# FMC_HPC2.net
KiCad netlist of a schematic drawn in Altium Designer
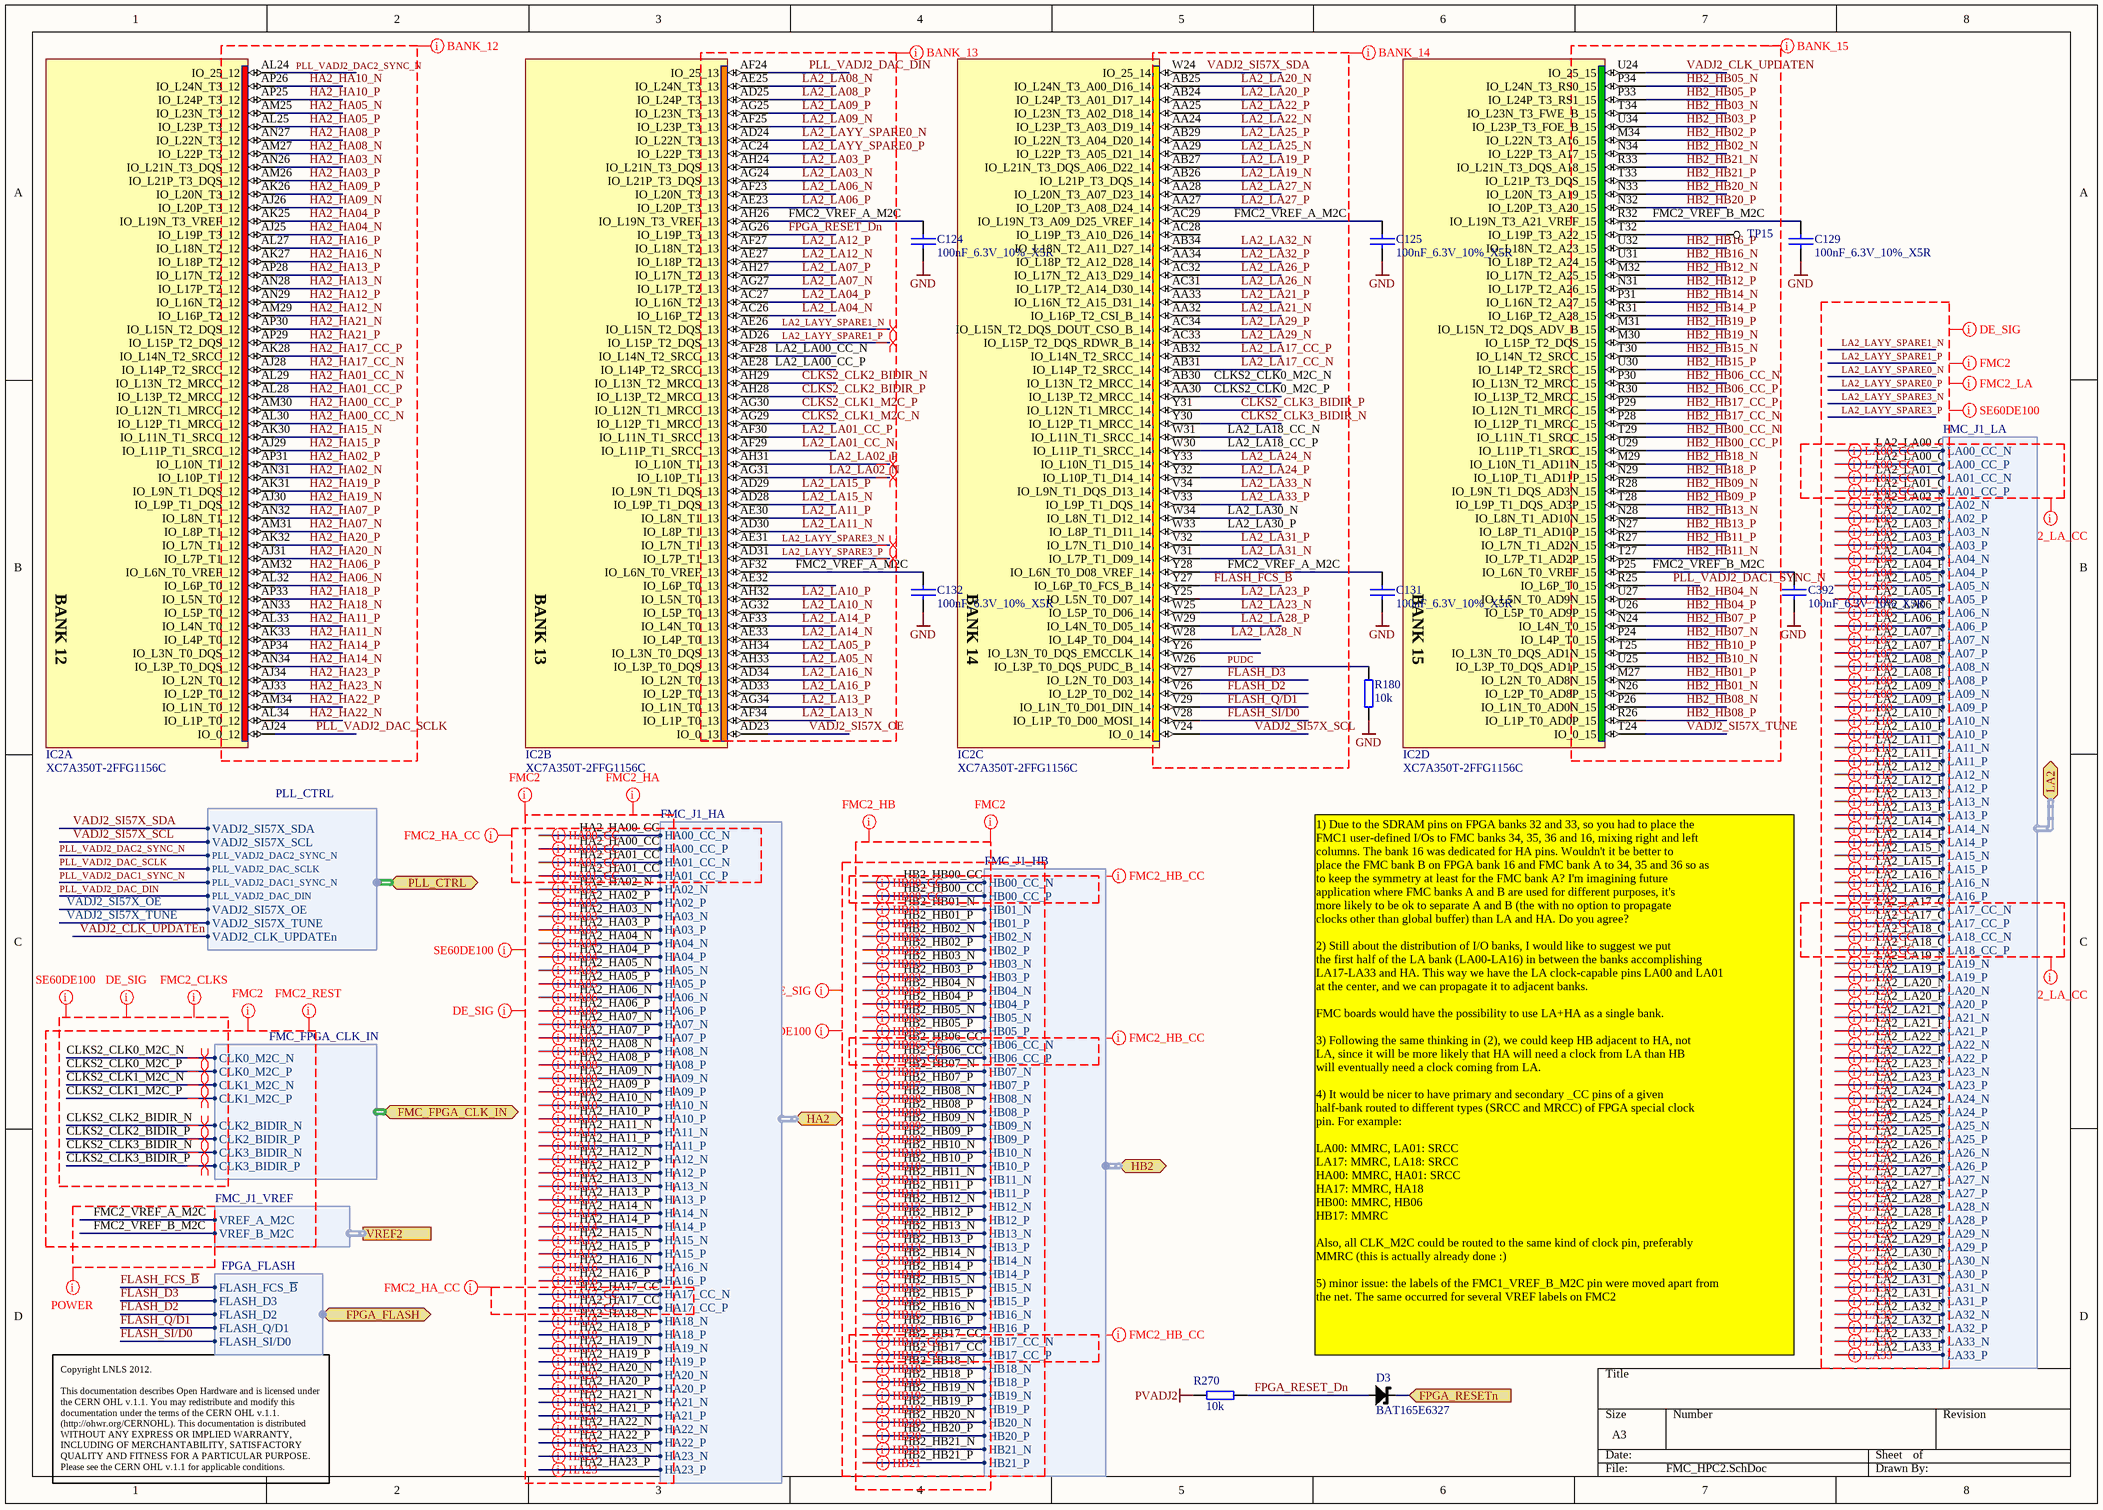
[diagram p0: FMC_HPC2.SchDoc]

(export (version "E")
  (design (tool "Eeschema 10.0.6"))
  (components
    (comp (ref "C124")
      (value "100nF_6.3V_10%_X5R")
      (footprint "0201C")
      (description "Capacitor SMD")
      (libsource (lib "LIBRARY_SCH") (part "CAP_SMD_0201"))
    )
    (comp (ref "C125")
      (value "100nF_6.3V_10%_X5R")
      (footprint "0201C")
      (description "Capacitor SMD")
      (libsource (lib "LIBRARY_SCH") (part "CAP_SMD_0201"))
    )
    (comp (ref "C129")
      (value "100nF_6.3V_10%_X5R")
      (footprint "0201C")
      (description "Capacitor SMD")
      (libsource (lib "LIBRARY_SCH") (part "CAP_SMD_0201"))
    )
    (comp (ref "C131")
      (value "100nF_6.3V_10%_X5R")
      (footprint "0201C")
      (description "Capacitor SMD")
      (libsource (lib "LIBRARY_SCH") (part "CAP_SMD_0201"))
    )
    (comp (ref "C132")
      (value "100nF_6.3V_10%_X5R")
      (footprint "0201C")
      (description "Capacitor SMD")
      (libsource (lib "LIBRARY_SCH") (part "CAP_SMD_0201"))
    )
    (comp (ref "C392")
      (value "100nF_6.3V_10%_X5R")
      (footprint "0201C")
      (description "Capacitor SMD")
      (libsource (lib "LIBRARY_SCH") (part "CAP_SMD_0201"))
    )
    (comp (ref "D3")
      (value "BAT165E6327")
      (footprint "SOD323")
      (description "500mA, 40V, Shottky Diode")
      (libsource (lib "LIBRARY_SCH") (part "D_BAT165"))
    )
    (comp (ref "IC2")
      (value "XC7A350T-2FFG1156C")
      (footprint "BGA1156C100P34X34_3500X3500X335")
      (description "Artix-6 FPGA, 16 GTPs, 600 User I/Os, 1156-Pin BGA, Speed Grade 2, Commercial Grade, Pb-Free")
      (fields (field (name "MANUFACTURER") "XILINX") (field (name "AUTHOR") "CERN DEM JLC"))
      (libsource (lib "AMC_FMC_Carrier") (part "XC7A350T-2FFG1156C"))
    )
    (comp (ref "R180")
      (value "10k")
      (footprint "0402R")
      (description "SMD Resistor")
      (libsource (lib "LIBRARY_SCH") (part "RES_0402"))
    )
    (comp (ref "R270")
      (value "10k")
      (footprint "0402R")
      (description "SMD Resistor")
      (libsource (lib "LIBRARY_SCH") (part "RES_0402"))
    )
    (comp (ref "TP15")
      (value "TP")
      (footprint "TP_large")
      (description "Testpoint")
      (libsource (lib "LIBRARY_SCH") (part "TP"))
    )
  )
  (nets
    (net (code "8") (name "/CLKS2_CLK0_M2C_N") (class "Default")
      (node (ref "IC2") (pin "AB30") (pinfunction "IO_L13N_T2_MRCC_14_AB30") (pintype "bidirectional"))
    )
    (net (code "9") (name "/CLKS2_CLK0_M2C_P") (class "Default")
      (node (ref "IC2") (pin "AA30") (pinfunction "IO_L13P_T2_MRCC_14_AA30") (pintype "bidirectional"))
    )
    (net (code "10") (name "/CLKS2_CLK1_M2C_N") (class "Default")
      (node (ref "IC2") (pin "AG29") (pinfunction "IO_L12P_T1_MRCC_13_AG29") (pintype "bidirectional"))
    )
    (net (code "11") (name "/CLKS2_CLK1_M2C_P") (class "Default")
      (node (ref "IC2") (pin "AG30") (pinfunction "IO_L12N_T1_MRCC_13_AG30") (pintype "bidirectional"))
    )
    (net (code "12") (name "/CLKS2_CLK2_BIDIR_N") (class "Default")
      (node (ref "IC2") (pin "AH29") (pinfunction "IO_L13N_T2_MRCC_13_AH29") (pintype "bidirectional"))
    )
    (net (code "13") (name "/CLKS2_CLK2_BIDIR_P") (class "Default")
      (node (ref "IC2") (pin "AH28") (pinfunction "IO_L13P_T2_MRCC_13_AH28") (pintype "bidirectional"))
    )
    (net (code "14") (name "/CLKS2_CLK3_BIDIR_N") (class "Default")
      (node (ref "IC2") (pin "Y30") (pinfunction "IO_L12P_T1_MRCC_14_Y30") (pintype "bidirectional"))
    )
    (net (code "15") (name "/CLKS2_CLK3_BIDIR_P") (class "Default")
      (node (ref "IC2") (pin "Y31") (pinfunction "IO_L12N_T1_MRCC_14_Y31") (pintype "bidirectional"))
    )
    (net (code "16") (name "/FLASH_D2") (class "Default")
      (node (ref "IC2") (pin "V26") (pinfunction "IO_L2P_T0_D02_14_V26") (pintype "bidirectional"))
    )
    (net (code "17") (name "/FLASH_D3") (class "Default")
      (node (ref "IC2") (pin "V27") (pinfunction "IO_L2N_T0_D03_14_V27") (pintype "bidirectional"))
    )
    (net (code "18") (name "/FLASH_FCS_~{B}") (class "Default")
      (node (ref "IC2") (pin "Y27") (pinfunction "IO_L6P_T0_FCS_B_14_Y27") (pintype "bidirectional"))
    )
    (net (code "19") (name "/FLASH_Q{slash}D1") (class "Default")
      (node (ref "IC2") (pin "V29") (pinfunction "IO_L1N_T0_D01_DIN_14_V29") (pintype "bidirectional"))
    )
    (net (code "20") (name "/FLASH_SI{slash}D0") (class "Default")
      (node (ref "IC2") (pin "V28") (pinfunction "IO_L1P_T0_D00_MOSI_14_V28") (pintype "bidirectional"))
    )
    (net (code "21") (name "/FMC2_VREF_A_M2C") (class "Default")
      (node (ref "C124") (pin "1") (pinfunction "1_1") (pintype "passive"))
      (node (ref "C125") (pin "1") (pinfunction "1_1") (pintype "passive"))
      (node (ref "C131") (pin "1") (pinfunction "1_1") (pintype "passive"))
      (node (ref "C132") (pin "1") (pinfunction "1_1") (pintype "passive"))
      (node (ref "IC2") (pin "AC29") (pinfunction "IO_L19N_T3_A09_D25_VREF_14_AC29") (pintype "bidirectional"))
      (node (ref "IC2") (pin "AF32") (pinfunction "IO_L6N_T0_VREF_13_AF32") (pintype "bidirectional"))
      (node (ref "IC2") (pin "AH26") (pinfunction "IO_L19N_T3_VREF_13_AH26") (pintype "bidirectional"))
      (node (ref "IC2") (pin "Y28") (pinfunction "IO_L6N_T0_D08_VREF_14_Y28") (pintype "bidirectional"))
    )
    (net (code "22") (name "/FMC2_VREF_B_M2C") (class "Default")
      (node (ref "C129") (pin "1") (pinfunction "1_1") (pintype "passive"))
      (node (ref "C392") (pin "1") (pinfunction "1_1") (pintype "passive"))
      (node (ref "IC2") (pin "P25") (pinfunction "IO_L6N_T0_VREF_15_P25") (pintype "bidirectional"))
      (node (ref "IC2") (pin "R32") (pinfunction "IO_L19N_T3_A21_VREF_15_R32") (pintype "bidirectional"))
    )
    (net (code "23") (name "/FPGA_RESET_Dn") (class "Default")
      (node (ref "D3") (pin "A") (pinfunction "A_A") (pintype "passive"))
      (node (ref "IC2") (pin "AG26") (pinfunction "IO_L19P_T3_13_AG26") (pintype "bidirectional"))
      (node (ref "R270") (pin "2") (pinfunction "2_2") (pintype "passive"))
    )
    (net (code "24") (name "/FPGA_RESETn") (class "Default")
      (node (ref "D3") (pin "K") (pinfunction "K_K") (pintype "passive"))
    )
    (net (code "25") (name "/HA2_HA00_CC_N") (class "Default")
      (node (ref "IC2") (pin "AL30") (pinfunction "IO_L12P_T1_MRCC_12_AL30") (pintype "bidirectional"))
    )
    (net (code "26") (name "/HA2_HA00_CC_P") (class "Default")
      (node (ref "IC2") (pin "AM30") (pinfunction "IO_L12N_T1_MRCC_12_AM30") (pintype "bidirectional"))
    )
    (net (code "27") (name "/HA2_HA01_CC_N") (class "Default")
      (node (ref "IC2") (pin "AL29") (pinfunction "IO_L13N_T2_MRCC_12_AL29") (pintype "bidirectional"))
    )
    (net (code "28") (name "/HA2_HA01_CC_P") (class "Default")
      (node (ref "IC2") (pin "AL28") (pinfunction "IO_L13P_T2_MRCC_12_AL28") (pintype "bidirectional"))
    )
    (net (code "29") (name "/HA2_HA02_N") (class "Default")
      (node (ref "IC2") (pin "AN31") (pinfunction "IO_L10P_T1_12_AN31") (pintype "bidirectional"))
    )
    (net (code "30") (name "/HA2_HA02_P") (class "Default")
      (node (ref "IC2") (pin "AP31") (pinfunction "IO_L10N_T1_12_AP31") (pintype "bidirectional"))
    )
    (net (code "31") (name "/HA2_HA03_N") (class "Default")
      (node (ref "IC2") (pin "AN26") (pinfunction "IO_L21N_T3_DQS_12_AN26") (pintype "bidirectional"))
    )
    (net (code "32") (name "/HA2_HA03_P") (class "Default")
      (node (ref "IC2") (pin "AM26") (pinfunction "IO_L21P_T3_DQS_12_AM26") (pintype "bidirectional"))
    )
    (net (code "33") (name "/HA2_HA04_N") (class "Default")
      (node (ref "IC2") (pin "AJ25") (pinfunction "IO_L19P_T3_12_AJ25") (pintype "bidirectional"))
    )
    (net (code "34") (name "/HA2_HA04_P") (class "Default")
      (node (ref "IC2") (pin "AK25") (pinfunction "IO_L19N_T3_VREF_12_AK25") (pintype "bidirectional"))
    )
    (net (code "35") (name "/HA2_HA05_N") (class "Default")
      (node (ref "IC2") (pin "AM25") (pinfunction "IO_L23N_T3_12_AM25") (pintype "bidirectional"))
    )
    (net (code "36") (name "/HA2_HA05_P") (class "Default")
      (node (ref "IC2") (pin "AL25") (pinfunction "IO_L23P_T3_12_AL25") (pintype "bidirectional"))
    )
    (net (code "37") (name "/HA2_HA06_N") (class "Default")
      (node (ref "IC2") (pin "AL32") (pinfunction "IO_L6P_T0_12_AL32") (pintype "bidirectional"))
    )
    (net (code "38") (name "/HA2_HA06_P") (class "Default")
      (node (ref "IC2") (pin "AM32") (pinfunction "IO_L6N_T0_VREF_12_AM32") (pintype "bidirectional"))
    )
    (net (code "39") (name "/HA2_HA07_N") (class "Default")
      (node (ref "IC2") (pin "AM31") (pinfunction "IO_L8P_T1_12_AM31") (pintype "bidirectional"))
    )
    (net (code "40") (name "/HA2_HA07_P") (class "Default")
      (node (ref "IC2") (pin "AN32") (pinfunction "IO_L8N_T1_12_AN32") (pintype "bidirectional"))
    )
    (net (code "41") (name "/HA2_HA08_N") (class "Default")
      (node (ref "IC2") (pin "AM27") (pinfunction "IO_L22P_T3_12_AM27") (pintype "bidirectional"))
    )
    (net (code "42") (name "/HA2_HA08_P") (class "Default")
      (node (ref "IC2") (pin "AN27") (pinfunction "IO_L22N_T3_12_AN27") (pintype "bidirectional"))
    )
    (net (code "43") (name "/HA2_HA09_N") (class "Default")
      (node (ref "IC2") (pin "AJ26") (pinfunction "IO_L20P_T3_12_AJ26") (pintype "bidirectional"))
    )
    (net (code "44") (name "/HA2_HA09_P") (class "Default")
      (node (ref "IC2") (pin "AK26") (pinfunction "IO_L20N_T3_12_AK26") (pintype "bidirectional"))
    )
    (net (code "45") (name "/HA2_HA10_N") (class "Default")
      (node (ref "IC2") (pin "AP26") (pinfunction "IO_L24N_T3_12_AP26") (pintype "bidirectional"))
    )
    (net (code "46") (name "/HA2_HA10_P") (class "Default")
      (node (ref "IC2") (pin "AP25") (pinfunction "IO_L24P_T3_12_AP25") (pintype "bidirectional"))
    )
    (net (code "47") (name "/HA2_HA11_N") (class "Default")
      (node (ref "IC2") (pin "AK33") (pinfunction "IO_L4P_T0_12_AK33") (pintype "bidirectional"))
    )
    (net (code "48") (name "/HA2_HA11_P") (class "Default")
      (node (ref "IC2") (pin "AL33") (pinfunction "IO_L4N_T0_12_AL33") (pintype "bidirectional"))
    )
    (net (code "49") (name "/HA2_HA12_N") (class "Default")
      (node (ref "IC2") (pin "AM29") (pinfunction "IO_L16P_T2_12_AM29") (pintype "bidirectional"))
    )
    (net (code "50") (name "/HA2_HA12_P") (class "Default")
      (node (ref "IC2") (pin "AN29") (pinfunction "IO_L16N_T2_12_AN29") (pintype "bidirectional"))
    )
    (net (code "51") (name "/HA2_HA13_N") (class "Default")
      (node (ref "IC2") (pin "AN28") (pinfunction "IO_L17P_T2_12_AN28") (pintype "bidirectional"))
    )
    (net (code "52") (name "/HA2_HA13_P") (class "Default")
      (node (ref "IC2") (pin "AP28") (pinfunction "IO_L17N_T2_12_AP28") (pintype "bidirectional"))
    )
    (net (code "53") (name "/HA2_HA14_N") (class "Default")
      (node (ref "IC2") (pin "AN34") (pinfunction "IO_L3P_T0_DQS_12_AN34") (pintype "bidirectional"))
    )
    (net (code "54") (name "/HA2_HA14_P") (class "Default")
      (node (ref "IC2") (pin "AP34") (pinfunction "IO_L3N_T0_DQS_12_AP34") (pintype "bidirectional"))
    )
    (net (code "55") (name "/HA2_HA15_N") (class "Default")
      (node (ref "IC2") (pin "AK30") (pinfunction "IO_L11N_T1_SRCC_12_AK30") (pintype "bidirectional"))
    )
    (net (code "56") (name "/HA2_HA15_P") (class "Default")
      (node (ref "IC2") (pin "AJ29") (pinfunction "IO_L11P_T1_SRCC_12_AJ29") (pintype "bidirectional"))
    )
    (net (code "57") (name "/HA2_HA16_N") (class "Default")
      (node (ref "IC2") (pin "AK27") (pinfunction "IO_L18P_T2_12_AK27") (pintype "bidirectional"))
    )
    (net (code "58") (name "/HA2_HA16_P") (class "Default")
      (node (ref "IC2") (pin "AL27") (pinfunction "IO_L18N_T2_12_AL27") (pintype "bidirectional"))
    )
    (net (code "59") (name "/HA2_HA17_CC_N") (class "Default")
      (node (ref "IC2") (pin "AJ28") (pinfunction "IO_L14P_T2_SRCC_12_AJ28") (pintype "bidirectional"))
    )
    (net (code "60") (name "/HA2_HA17_CC_P") (class "Default")
      (node (ref "IC2") (pin "AK28") (pinfunction "IO_L14N_T2_SRCC_12_AK28") (pintype "bidirectional"))
    )
    (net (code "61") (name "/HA2_HA18_N") (class "Default")
      (node (ref "IC2") (pin "AN33") (pinfunction "IO_L5P_T0_12_AN33") (pintype "bidirectional"))
    )
    (net (code "62") (name "/HA2_HA18_P") (class "Default")
      (node (ref "IC2") (pin "AP33") (pinfunction "IO_L5N_T0_12_AP33") (pintype "bidirectional"))
    )
    (net (code "63") (name "/HA2_HA19_N") (class "Default")
      (node (ref "IC2") (pin "AJ30") (pinfunction "IO_L9P_T1_DQS_12_AJ30") (pintype "bidirectional"))
    )
    (net (code "64") (name "/HA2_HA19_P") (class "Default")
      (node (ref "IC2") (pin "AK31") (pinfunction "IO_L9N_T1_DQS_12_AK31") (pintype "bidirectional"))
    )
    (net (code "65") (name "/HA2_HA20_N") (class "Default")
      (node (ref "IC2") (pin "AJ31") (pinfunction "IO_L7P_T1_12_AJ31") (pintype "bidirectional"))
    )
    (net (code "66") (name "/HA2_HA20_P") (class "Default")
      (node (ref "IC2") (pin "AK32") (pinfunction "IO_L7N_T1_12_AK32") (pintype "bidirectional"))
    )
    (net (code "67") (name "/HA2_HA21_N") (class "Default")
      (node (ref "IC2") (pin "AP30") (pinfunction "IO_L15N_T2_DQS_12_AP30") (pintype "bidirectional"))
    )
    (net (code "68") (name "/HA2_HA21_P") (class "Default")
      (node (ref "IC2") (pin "AP29") (pinfunction "IO_L15P_T2_DQS_12_AP29") (pintype "bidirectional"))
    )
    (net (code "69") (name "/HA2_HA22_N") (class "Default")
      (node (ref "IC2") (pin "AL34") (pinfunction "IO_L1P_T0_12_AL34") (pintype "bidirectional"))
    )
    (net (code "70") (name "/HA2_HA22_P") (class "Default")
      (node (ref "IC2") (pin "AM34") (pinfunction "IO_L1N_T0_12_AM34") (pintype "bidirectional"))
    )
    (net (code "71") (name "/HA2_HA23_N") (class "Default")
      (node (ref "IC2") (pin "AJ33") (pinfunction "IO_L2P_T0_12_AJ33") (pintype "bidirectional"))
    )
    (net (code "72") (name "/HA2_HA23_P") (class "Default")
      (node (ref "IC2") (pin "AJ34") (pinfunction "IO_L2N_T0_12_AJ34") (pintype "bidirectional"))
    )
    (net (code "73") (name "/HB2_HB00_CC_N") (class "Default")
      (node (ref "IC2") (pin "T29") (pinfunction "IO_L11N_T1_SRCC_15_T29") (pintype "bidirectional"))
    )
    (net (code "74") (name "/HB2_HB00_CC_P") (class "Default")
      (node (ref "IC2") (pin "U29") (pinfunction "IO_L11P_T1_SRCC_15_U29") (pintype "bidirectional"))
    )
    (net (code "75") (name "/HB2_HB01_N") (class "Default")
      (node (ref "IC2") (pin "N26") (pinfunction "IO_L2P_T0_AD8P_15_N26") (pintype "bidirectional"))
    )
    (net (code "76") (name "/HB2_HB01_P") (class "Default")
      (node (ref "IC2") (pin "M27") (pinfunction "IO_L2N_T0_AD8N_15_M27") (pintype "bidirectional"))
    )
    (net (code "77") (name "/HB2_HB02_N") (class "Default")
      (node (ref "IC2") (pin "N34") (pinfunction "IO_L22P_T3_A17_15_N34") (pintype "bidirectional"))
    )
    (net (code "78") (name "/HB2_HB02_P") (class "Default")
      (node (ref "IC2") (pin "M34") (pinfunction "IO_L22N_T3_A16_15_M34") (pintype "bidirectional"))
    )
    (net (code "79") (name "/HB2_HB03_N") (class "Default")
      (node (ref "IC2") (pin "T34") (pinfunction "IO_L23N_T3_FWE_B_15_T34") (pintype "bidirectional"))
    )
    (net (code "80") (name "/HB2_HB03_P") (class "Default")
      (node (ref "IC2") (pin "U34") (pinfunction "IO_L23P_T3_FOE_B_15_U34") (pintype "bidirectional"))
    )
    (net (code "81") (name "/HB2_HB04_N") (class "Default")
      (node (ref "IC2") (pin "U27") (pinfunction "IO_L5N_T0_AD9N_15_U27") (pintype "bidirectional"))
    )
    (net (code "82") (name "/HB2_HB04_P") (class "Default")
      (node (ref "IC2") (pin "U26") (pinfunction "IO_L5P_T0_AD9P_15_U26") (pintype "bidirectional"))
    )
    (net (code "83") (name "/HB2_HB05_N") (class "Default")
      (node (ref "IC2") (pin "P34") (pinfunction "IO_L24N_T3_RS0_15_P34") (pintype "bidirectional"))
    )
    (net (code "84") (name "/HB2_HB05_P") (class "Default")
      (node (ref "IC2") (pin "P33") (pinfunction "IO_L24P_T3_RS1_15_P33") (pintype "bidirectional"))
    )
    (net (code "85") (name "/HB2_HB06_CC_N") (class "Default")
      (node (ref "IC2") (pin "P30") (pinfunction "IO_L13N_T2_MRCC_15_P30") (pintype "bidirectional"))
    )
    (net (code "86") (name "/HB2_HB06_CC_P") (class "Default")
      (node (ref "IC2") (pin "R30") (pinfunction "IO_L13P_T2_MRCC_15_R30") (pintype "bidirectional"))
    )
    (net (code "87") (name "/HB2_HB07_N") (class "Default")
      (node (ref "IC2") (pin "P24") (pinfunction "IO_L4P_T0_15_P24") (pintype "bidirectional"))
    )
    (net (code "88") (name "/HB2_HB07_P") (class "Default")
      (node (ref "IC2") (pin "N24") (pinfunction "IO_L4N_T0_15_N24") (pintype "bidirectional"))
    )
    (net (code "89") (name "/HB2_HB08_N") (class "Default")
      (node (ref "IC2") (pin "P26") (pinfunction "IO_L1N_T0_AD0N_15_P26") (pintype "bidirectional"))
    )
    (net (code "90") (name "/HB2_HB08_P") (class "Default")
      (node (ref "IC2") (pin "R26") (pinfunction "IO_L1P_T0_AD0P_15_R26") (pintype "bidirectional"))
    )
    (net (code "91") (name "/HB2_HB09_N") (class "Default")
      (node (ref "IC2") (pin "R28") (pinfunction "IO_L9N_T1_DQS_AD3N_15_R28") (pintype "bidirectional"))
    )
    (net (code "92") (name "/HB2_HB09_P") (class "Default")
      (node (ref "IC2") (pin "T28") (pinfunction "IO_L9P_T1_DQS_AD3P_15_T28") (pintype "bidirectional"))
    )
    (net (code "93") (name "/HB2_HB10_N") (class "Default")
      (node (ref "IC2") (pin "U25") (pinfunction "IO_L3P_T0_DQS_AD1P_15_U25") (pintype "bidirectional"))
    )
    (net (code "94") (name "/HB2_HB10_P") (class "Default")
      (node (ref "IC2") (pin "T25") (pinfunction "IO_L3N_T0_DQS_AD1N_15_T25") (pintype "bidirectional"))
    )
    (net (code "95") (name "/HB2_HB11_N") (class "Default")
      (node (ref "IC2") (pin "T27") (pinfunction "IO_L7P_T1_AD2P_15_T27") (pintype "bidirectional"))
    )
    (net (code "96") (name "/HB2_HB11_P") (class "Default")
      (node (ref "IC2") (pin "R27") (pinfunction "IO_L7N_T1_AD2N_15_R27") (pintype "bidirectional"))
    )
    (net (code "97") (name "/HB2_HB12_N") (class "Default")
      (node (ref "IC2") (pin "M32") (pinfunction "IO_L17N_T2_A25_15_M32") (pintype "bidirectional"))
    )
    (net (code "98") (name "/HB2_HB12_P") (class "Default")
      (node (ref "IC2") (pin "N31") (pinfunction "IO_L17P_T2_A26_15_N31") (pintype "bidirectional"))
    )
    (net (code "99") (name "/HB2_HB13_N") (class "Default")
      (node (ref "IC2") (pin "N28") (pinfunction "IO_L8N_T1_AD10N_15_N28") (pintype "bidirectional"))
    )
    (net (code "100") (name "/HB2_HB13_P") (class "Default")
      (node (ref "IC2") (pin "N27") (pinfunction "IO_L8P_T1_AD10P_15_N27") (pintype "bidirectional"))
    )
    (net (code "101") (name "/HB2_HB14_N") (class "Default")
      (node (ref "IC2") (pin "P31") (pinfunction "IO_L16N_T2_A27_15_P31") (pintype "bidirectional"))
    )
    (net (code "102") (name "/HB2_HB14_P") (class "Default")
      (node (ref "IC2") (pin "R31") (pinfunction "IO_L16P_T2_A28_15_R31") (pintype "bidirectional"))
    )
    (net (code "103") (name "/HB2_HB15_N") (class "Default")
      (node (ref "IC2") (pin "T30") (pinfunction "IO_L14N_T2_SRCC_15_T30") (pintype "bidirectional"))
    )
    (net (code "104") (name "/HB2_HB15_P") (class "Default")
      (node (ref "IC2") (pin "U30") (pinfunction "IO_L14P_T2_SRCC_15_U30") (pintype "bidirectional"))
    )
    (net (code "105") (name "/HB2_HB16_N") (class "Default")
      (node (ref "IC2") (pin "U31") (pinfunction "IO_L18P_T2_A24_15_U31") (pintype "bidirectional"))
    )
    (net (code "106") (name "/HB2_HB16_P") (class "Default")
      (node (ref "IC2") (pin "U32") (pinfunction "IO_L18N_T2_A23_15_U32") (pintype "bidirectional"))
    )
    (net (code "107") (name "/HB2_HB17_CC_N") (class "Default")
      (node (ref "IC2") (pin "P28") (pinfunction "IO_L12P_T1_MRCC_15_P28") (pintype "bidirectional"))
    )
    (net (code "108") (name "/HB2_HB17_CC_P") (class "Default")
      (node (ref "IC2") (pin "P29") (pinfunction "IO_L12N_T1_MRCC_15_P29") (pintype "bidirectional"))
    )
    (net (code "109") (name "/HB2_HB18_N") (class "Default")
      (node (ref "IC2") (pin "M29") (pinfunction "IO_L10N_T1_AD11N_15_M29") (pintype "bidirectional"))
    )
    (net (code "110") (name "/HB2_HB18_P") (class "Default")
      (node (ref "IC2") (pin "N29") (pinfunction "IO_L10P_T1_AD11P_15_N29") (pintype "bidirectional"))
    )
    (net (code "111") (name "/HB2_HB19_N") (class "Default")
      (node (ref "IC2") (pin "M30") (pinfunction "IO_L15P_T2_DQS_15_M30") (pintype "bidirectional"))
    )
    (net (code "112") (name "/HB2_HB19_P") (class "Default")
      (node (ref "IC2") (pin "M31") (pinfunction "IO_L15N_T2_DQS_ADV_B_15_M31") (pintype "bidirectional"))
    )
    (net (code "113") (name "/HB2_HB20_N") (class "Default")
      (node (ref "IC2") (pin "N33") (pinfunction "IO_L20N_T3_A19_15_N33") (pintype "bidirectional"))
    )
    (net (code "114") (name "/HB2_HB20_P") (class "Default")
      (node (ref "IC2") (pin "N32") (pinfunction "IO_L20P_T3_A20_15_N32") (pintype "bidirectional"))
    )
    (net (code "115") (name "/HB2_HB21_N") (class "Default")
      (node (ref "IC2") (pin "R33") (pinfunction "IO_L21N_T3_DQS_A18_15_R33") (pintype "bidirectional"))
    )
    (net (code "116") (name "/HB2_HB21_P") (class "Default")
      (node (ref "IC2") (pin "T33") (pinfunction "IO_L21P_T3_DQS_15_T33") (pintype "bidirectional"))
    )
    (net (code "117") (name "/LA2_LA00_CC_N") (class "Default")
      (node (ref "IC2") (pin "AF28") (pinfunction "IO_L14N_T2_SRCC_13_AF28") (pintype "bidirectional"))
    )
    (net (code "118") (name "/LA2_LA00_CC_P") (class "Default")
      (node (ref "IC2") (pin "AE28") (pinfunction "IO_L14P_T2_SRCC_13_AE28") (pintype "bidirectional"))
    )
    (net (code "119") (name "/LA2_LA01_CC_N") (class "Default")
      (node (ref "IC2") (pin "AF29") (pinfunction "IO_L11P_T1_SRCC_13_AF29") (pintype "bidirectional"))
    )
    (net (code "120") (name "/LA2_LA01_CC_P") (class "Default")
      (node (ref "IC2") (pin "AF30") (pinfunction "IO_L11N_T1_SRCC_13_AF30") (pintype "bidirectional"))
    )
    (net (code "121") (name "/LA2_LA02_N") (class "Default")
      (node (ref "IC2") (pin "AG31") (pinfunction "IO_L10P_T1_13_AG31") (pintype "bidirectional"))
    )
    (net (code "122") (name "/LA2_LA02_P") (class "Default")
      (node (ref "IC2") (pin "AH31") (pinfunction "IO_L10N_T1_13_AH31") (pintype "bidirectional"))
    )
    (net (code "123") (name "/LA2_LA03_N") (class "Default")
      (node (ref "IC2") (pin "AG24") (pinfunction "IO_L21P_T3_DQS_13_AG24") (pintype "bidirectional"))
    )
    (net (code "124") (name "/LA2_LA03_P") (class "Default")
      (node (ref "IC2") (pin "AH24") (pinfunction "IO_L21N_T3_DQS_13_AH24") (pintype "bidirectional"))
    )
    (net (code "125") (name "/LA2_LA04_N") (class "Default")
      (node (ref "IC2") (pin "AC26") (pinfunction "IO_L16P_T2_13_AC26") (pintype "bidirectional"))
    )
    (net (code "126") (name "/LA2_LA04_P") (class "Default")
      (node (ref "IC2") (pin "AC27") (pinfunction "IO_L16N_T2_13_AC27") (pintype "bidirectional"))
    )
    (net (code "127") (name "/LA2_LA05_N") (class "Default")
      (node (ref "IC2") (pin "AH33") (pinfunction "IO_L3P_T0_DQS_13_AH33") (pintype "bidirectional"))
    )
    (net (code "128") (name "/LA2_LA05_P") (class "Default")
      (node (ref "IC2") (pin "AH34") (pinfunction "IO_L3N_T0_DQS_13_AH34") (pintype "bidirectional"))
    )
    (net (code "129") (name "/LA2_LA06_N") (class "Default")
      (node (ref "IC2") (pin "AF23") (pinfunction "IO_L20N_T3_13_AF23") (pintype "bidirectional"))
    )
    (net (code "130") (name "/LA2_LA06_P") (class "Default")
      (node (ref "IC2") (pin "AE23") (pinfunction "IO_L20P_T3_13_AE23") (pintype "bidirectional"))
    )
    (net (code "131") (name "/LA2_LA07_N") (class "Default")
      (node (ref "IC2") (pin "AG27") (pinfunction "IO_L17P_T2_13_AG27") (pintype "bidirectional"))
    )
    (net (code "132") (name "/LA2_LA07_P") (class "Default")
      (node (ref "IC2") (pin "AH27") (pinfunction "IO_L17N_T2_13_AH27") (pintype "bidirectional"))
    )
    (net (code "133") (name "/LA2_LA08_N") (class "Default")
      (node (ref "IC2") (pin "AE25") (pinfunction "IO_L24N_T3_13_AE25") (pintype "bidirectional"))
    )
    (net (code "134") (name "/LA2_LA08_P") (class "Default")
      (node (ref "IC2") (pin "AD25") (pinfunction "IO_L24P_T3_13_AD25") (pintype "bidirectional"))
    )
    (net (code "135") (name "/LA2_LA09_N") (class "Default")
      (node (ref "IC2") (pin "AF25") (pinfunction "IO_L23P_T3_13_AF25") (pintype "bidirectional"))
    )
    (net (code "136") (name "/LA2_LA09_P") (class "Default")
      (node (ref "IC2") (pin "AG25") (pinfunction "IO_L23N_T3_13_AG25") (pintype "bidirectional"))
    )
    (net (code "137") (name "/LA2_LA10_N") (class "Default")
      (node (ref "IC2") (pin "AG32") (pinfunction "IO_L5P_T0_13_AG32") (pintype "bidirectional"))
    )
    (net (code "138") (name "/LA2_LA10_P") (class "Default")
      (node (ref "IC2") (pin "AH32") (pinfunction "IO_L5N_T0_13_AH32") (pintype "bidirectional"))
    )
    (net (code "139") (name "/LA2_LA11_N") (class "Default")
      (node (ref "IC2") (pin "AD30") (pinfunction "IO_L8P_T1_13_AD30") (pintype "bidirectional"))
    )
    (net (code "140") (name "/LA2_LA11_P") (class "Default")
      (node (ref "IC2") (pin "AE30") (pinfunction "IO_L8N_T1_13_AE30") (pintype "bidirectional"))
    )
    (net (code "141") (name "/LA2_LA12_N") (class "Default")
      (node (ref "IC2") (pin "AE27") (pinfunction "IO_L18P_T2_13_AE27") (pintype "bidirectional"))
    )
    (net (code "142") (name "/LA2_LA12_P") (class "Default")
      (node (ref "IC2") (pin "AF27") (pinfunction "IO_L18N_T2_13_AF27") (pintype "bidirectional"))
    )
    (net (code "143") (name "/LA2_LA13_N") (class "Default")
      (node (ref "IC2") (pin "AF34") (pinfunction "IO_L1P_T0_13_AF34") (pintype "bidirectional"))
    )
    (net (code "144") (name "/LA2_LA13_P") (class "Default")
      (node (ref "IC2") (pin "AG34") (pinfunction "IO_L1N_T0_13_AG34") (pintype "bidirectional"))
    )
    (net (code "145") (name "/LA2_LA14_N") (class "Default")
      (node (ref "IC2") (pin "AE33") (pinfunction "IO_L4P_T0_13_AE33") (pintype "bidirectional"))
    )
    (net (code "146") (name "/LA2_LA14_P") (class "Default")
      (node (ref "IC2") (pin "AF33") (pinfunction "IO_L4N_T0_13_AF33") (pintype "bidirectional"))
    )
    (net (code "147") (name "/LA2_LA15_N") (class "Default")
      (node (ref "IC2") (pin "AD28") (pinfunction "IO_L9P_T1_DQS_13_AD28") (pintype "bidirectional"))
    )
    (net (code "148") (name "/LA2_LA15_P") (class "Default")
      (node (ref "IC2") (pin "AD29") (pinfunction "IO_L9N_T1_DQS_13_AD29") (pintype "bidirectional"))
    )
    (net (code "149") (name "/LA2_LA16_N") (class "Default")
      (node (ref "IC2") (pin "AD34") (pinfunction "IO_L2N_T0_13_AD34") (pintype "bidirectional"))
    )
    (net (code "150") (name "/LA2_LA16_P") (class "Default")
      (node (ref "IC2") (pin "AD33") (pinfunction "IO_L2P_T0_13_AD33") (pintype "bidirectional"))
    )
    (net (code "151") (name "/LA2_LA17_CC_N") (class "Default")
      (node (ref "IC2") (pin "AB31") (pinfunction "IO_L14P_T2_SRCC_14_AB31") (pintype "bidirectional"))
    )
    (net (code "152") (name "/LA2_LA17_CC_P") (class "Default")
      (node (ref "IC2") (pin "AB32") (pinfunction "IO_L14N_T2_SRCC_14_AB32") (pintype "bidirectional"))
    )
    (net (code "153") (name "/LA2_LA18_CC_N") (class "Default")
      (node (ref "IC2") (pin "W31") (pinfunction "IO_L11N_T1_SRCC_14_W31") (pintype "bidirectional"))
    )
    (net (code "154") (name "/LA2_LA18_CC_P") (class "Default")
      (node (ref "IC2") (pin "W30") (pinfunction "IO_L11P_T1_SRCC_14_W30") (pintype "bidirectional"))
    )
    (net (code "155") (name "/LA2_LA19_N") (class "Default")
      (node (ref "IC2") (pin "AB26") (pinfunction "IO_L21P_T3_DQS_14_AB26") (pintype "bidirectional"))
    )
    (net (code "156") (name "/LA2_LA19_P") (class "Default")
      (node (ref "IC2") (pin "AB27") (pinfunction "IO_L21N_T3_DQS_A06_D22_14_AB27") (pintype "bidirectional"))
    )
    (net (code "157") (name "/LA2_LA20_N") (class "Default")
      (node (ref "IC2") (pin "AB25") (pinfunction "IO_L24N_T3_A00_D16_14_AB25") (pintype "bidirectional"))
    )
    (net (code "158") (name "/LA2_LA20_P") (class "Default")
      (node (ref "IC2") (pin "AB24") (pinfunction "IO_L24P_T3_A01_D17_14_AB24") (pintype "bidirectional"))
    )
    (net (code "159") (name "/LA2_LA21_N") (class "Default")
      (node (ref "IC2") (pin "AA32") (pinfunction "IO_L16P_T2_CSI_B_14_AA32") (pintype "bidirectional"))
    )
    (net (code "160") (name "/LA2_LA21_P") (class "Default")
      (node (ref "IC2") (pin "AA33") (pinfunction "IO_L16N_T2_A15_D31_14_AA33") (pintype "bidirectional"))
    )
    (net (code "161") (name "/LA2_LA22_N") (class "Default")
      (node (ref "IC2") (pin "AA24") (pinfunction "IO_L23P_T3_A03_D19_14_AA24") (pintype "bidirectional"))
    )
    (net (code "162") (name "/LA2_LA22_P") (class "Default")
      (node (ref "IC2") (pin "AA25") (pinfunction "IO_L23N_T3_A02_D18_14_AA25") (pintype "bidirectional"))
    )
    (net (code "163") (name "/LA2_LA23_N") (class "Default")
      (node (ref "IC2") (pin "W25") (pinfunction "IO_L5P_T0_D06_14_W25") (pintype "bidirectional"))
    )
    (net (code "164") (name "/LA2_LA23_P") (class "Default")
      (node (ref "IC2") (pin "Y25") (pinfunction "IO_L5N_T0_D07_14_Y25") (pintype "bidirectional"))
    )
    (net (code "165") (name "/LA2_LA24_N") (class "Default")
      (node (ref "IC2") (pin "Y33") (pinfunction "IO_L10N_T1_D15_14_Y33") (pintype "bidirectional"))
    )
    (net (code "166") (name "/LA2_LA24_P") (class "Default")
      (node (ref "IC2") (pin "Y32") (pinfunction "IO_L10P_T1_D14_14_Y32") (pintype "bidirectional"))
    )
    (net (code "167") (name "/LA2_LA25_N") (class "Default")
      (node (ref "IC2") (pin "AA29") (pinfunction "IO_L22P_T3_A05_D21_14_AA29") (pintype "bidirectional"))
    )
    (net (code "168") (name "/LA2_LA25_P") (class "Default")
      (node (ref "IC2") (pin "AB29") (pinfunction "IO_L22N_T3_A04_D20_14_AB29") (pintype "bidirectional"))
    )
    (net (code "169") (name "/LA2_LA26_N") (class "Default")
      (node (ref "IC2") (pin "AC31") (pinfunction "IO_L17P_T2_A14_D30_14_AC31") (pintype "bidirectional"))
    )
    (net (code "170") (name "/LA2_LA26_P") (class "Default")
      (node (ref "IC2") (pin "AC32") (pinfunction "IO_L17N_T2_A13_D29_14_AC32") (pintype "bidirectional"))
    )
    (net (code "171") (name "/LA2_LA27_N") (class "Default")
      (node (ref "IC2") (pin "AA28") (pinfunction "IO_L20N_T3_A07_D23_14_AA28") (pintype "bidirectional"))
    )
    (net (code "172") (name "/LA2_LA27_P") (class "Default")
      (node (ref "IC2") (pin "AA27") (pinfunction "IO_L20P_T3_A08_D24_14_AA27") (pintype "bidirectional"))
    )
    (net (code "173") (name "/LA2_LA28_N") (class "Default")
      (node (ref "IC2") (pin "W28") (pinfunction "IO_L4P_T0_D04_14_W28") (pintype "bidirectional"))
    )
    (net (code "174") (name "/LA2_LA28_P") (class "Default")
      (node (ref "IC2") (pin "W29") (pinfunction "IO_L4N_T0_D05_14_W29") (pintype "bidirectional"))
    )
    (net (code "175") (name "/LA2_LA29_N") (class "Default")
      (node (ref "IC2") (pin "AC33") (pinfunction "IO_L15P_T2_DQS_RDWR_B_14_AC33") (pintype "bidirectional"))
    )
    (net (code "176") (name "/LA2_LA29_P") (class "Default")
      (node (ref "IC2") (pin "AC34") (pinfunction "IO_L15N_T2_DQS_DOUT_CSO_B_14_AC34") (pintype "bidirectional"))
    )
    (net (code "177") (name "/LA2_LA30_N") (class "Default")
      (node (ref "IC2") (pin "W34") (pinfunction "IO_L8N_T1_D12_14_W34") (pintype "bidirectional"))
    )
    (net (code "178") (name "/LA2_LA30_P") (class "Default")
      (node (ref "IC2") (pin "W33") (pinfunction "IO_L8P_T1_D11_14_W33") (pintype "bidirectional"))
    )
    (net (code "179") (name "/LA2_LA31_N") (class "Default")
      (node (ref "IC2") (pin "V31") (pinfunction "IO_L7P_T1_D09_14_V31") (pintype "bidirectional"))
    )
    (net (code "180") (name "/LA2_LA31_P") (class "Default")
      (node (ref "IC2") (pin "V32") (pinfunction "IO_L7N_T1_D10_14_V32") (pintype "bidirectional"))
    )
    (net (code "181") (name "/LA2_LA32_N") (class "Default")
      (node (ref "IC2") (pin "AB34") (pinfunction "IO_L18N_T2_A11_D27_14_AB34") (pintype "bidirectional"))
    )
    (net (code "182") (name "/LA2_LA32_P") (class "Default")
      (node (ref "IC2") (pin "AA34") (pinfunction "IO_L18P_T2_A12_D28_14_AA34") (pintype "bidirectional"))
    )
    (net (code "183") (name "/LA2_LA33_N") (class "Default")
      (node (ref "IC2") (pin "V34") (pinfunction "IO_L9N_T1_DQS_D13_14_V34") (pintype "bidirectional"))
    )
    (net (code "184") (name "/LA2_LA33_P") (class "Default")
      (node (ref "IC2") (pin "V33") (pinfunction "IO_L9P_T1_DQS_14_V33") (pintype "bidirectional"))
    )
    (net (code "185") (name "/LA2_LAYY_SPARE0_N") (class "Default")
      (node (ref "IC2") (pin "AD24") (pinfunction "IO_L22N_T3_13_AD24") (pintype "bidirectional"))
    )
    (net (code "186") (name "/LA2_LAYY_SPARE0_P") (class "Default")
      (node (ref "IC2") (pin "AC24") (pinfunction "IO_L22P_T3_13_AC24") (pintype "bidirectional"))
    )
    (net (code "187") (name "/LA2_LAYY_SPARE1_N") (class "Default")
      (node (ref "IC2") (pin "AE26") (pinfunction "IO_L15N_T2_DQS_13_AE26") (pintype "bidirectional"))
    )
    (net (code "188") (name "/LA2_LAYY_SPARE1_P") (class "Default")
      (node (ref "IC2") (pin "AD26") (pinfunction "IO_L15P_T2_DQS_13_AD26") (pintype "bidirectional"))
    )
    (net (code "189") (name "/LA2_LAYY_SPARE3_N") (class "Default")
      (node (ref "IC2") (pin "AE31") (pinfunction "IO_L7N_T1_13_AE31") (pintype "bidirectional"))
    )
    (net (code "190") (name "/LA2_LAYY_SPARE3_P") (class "Default")
      (node (ref "IC2") (pin "AD31") (pinfunction "IO_L7P_T1_13_AD31") (pintype "bidirectional"))
    )
    (net (code "191") (name "/PLL_VADJ2_DAC1_SYNC_N") (class "Default")
      (node (ref "IC2") (pin "R25") (pinfunction "IO_L6P_T0_15_R25") (pintype "bidirectional"))
    )
    (net (code "192") (name "/PLL_VADJ2_DAC2_SYNC_N") (class "Default")
      (node (ref "IC2") (pin "AL24") (pinfunction "IO_25_12_AL24") (pintype "bidirectional"))
    )
    (net (code "193") (name "/PLL_VADJ2_DAC_DIN") (class "Default")
      (node (ref "IC2") (pin "AF24") (pinfunction "IO_25_13_AF24") (pintype "bidirectional"))
    )
    (net (code "194") (name "/PLL_VADJ2_DAC_SCLK") (class "Default")
      (node (ref "IC2") (pin "AJ24") (pinfunction "IO_0_12_AJ24") (pintype "bidirectional"))
    )
    (net (code "195") (name "/PUDC") (class "Default")
      (node (ref "IC2") (pin "W26") (pinfunction "IO_L3P_T0_DQS_PUDC_B_14_W26") (pintype "bidirectional"))
      (node (ref "R180") (pin "1") (pinfunction "1_1") (pintype "passive"))
    )
    (net (code "196") (name "/VADJ2_CLK_UPDATEN") (class "Default")
      (node (ref "IC2") (pin "U24") (pinfunction "IO_25_15_U24") (pintype "bidirectional"))
    )
    (net (code "198") (name "/VADJ2_SI57X_OE") (class "Default")
      (node (ref "IC2") (pin "AD23") (pinfunction "IO_0_13_AD23") (pintype "bidirectional"))
    )
    (net (code "199") (name "/VADJ2_SI57X_SCL") (class "Default")
      (node (ref "IC2") (pin "V24") (pinfunction "IO_0_14_V24") (pintype "bidirectional"))
    )
    (net (code "200") (name "/VADJ2_SI57X_SDA") (class "Default")
      (node (ref "IC2") (pin "W24") (pinfunction "IO_25_14_W24") (pintype "bidirectional"))
    )
    (net (code "201") (name "/VADJ2_SI57X_TUNE") (class "Default")
      (node (ref "IC2") (pin "T24") (pinfunction "IO_0_15_T24") (pintype "bidirectional"))
    )
    (net (code "209") (name "GND") (class "Default")
      (node (ref "C124") (pin "2") (pinfunction "2_2") (pintype "passive"))
      (node (ref "C125") (pin "2") (pinfunction "2_2") (pintype "passive"))
      (node (ref "C129") (pin "2") (pinfunction "2_2") (pintype "passive"))
      (node (ref "C131") (pin "2") (pinfunction "2_2") (pintype "passive"))
      (node (ref "C132") (pin "2") (pinfunction "2_2") (pintype "passive"))
      (node (ref "C392") (pin "2") (pinfunction "2_2") (pintype "passive"))
      (node (ref "R180") (pin "2") (pinfunction "2_2") (pintype "passive"))
    )
    (net (code "210") (name "Net-(IC2D-IO_L19P_T3_A22_15)") (class "Default")
      (node (ref "IC2") (pin "T32") (pinfunction "IO_L19P_T3_A22_15_T32") (pintype "bidirectional"))
      (node (ref "TP15") (pin "1") (pintype "passive"))
    )
    (net (code "211") (name "PVADJ2") (class "Default")
      (node (ref "R270") (pin "1") (pinfunction "1_1") (pintype "passive"))
    )
    (net (code "212") (name "unconnected-(IC2B-IO_L6P_T0_13-PadAE32)") (class "Default")
      (node (ref "IC2") (pin "AE32") (pinfunction "IO_L6P_T0_13_AE32") (pintype "bidirectional"))
    )
    (net (code "213") (name "unconnected-(IC2C-IO_L3N_T0_DQS_EMCCLK_14-PadY26)") (class "Default")
      (node (ref "IC2") (pin "Y26") (pinfunction "IO_L3N_T0_DQS_EMCCLK_14_Y26") (pintype "bidirectional"))
    )
    (net (code "214") (name "unconnected-(IC2C-IO_L19P_T3_A10_D26_14-PadAC28)") (class "Default")
      (node (ref "IC2") (pin "AC28") (pinfunction "IO_L19P_T3_A10_D26_14_AC28") (pintype "bidirectional"))
    )
  )
)
